# Prism.net
KiCad netlist of a schematic drawn in EAGLE
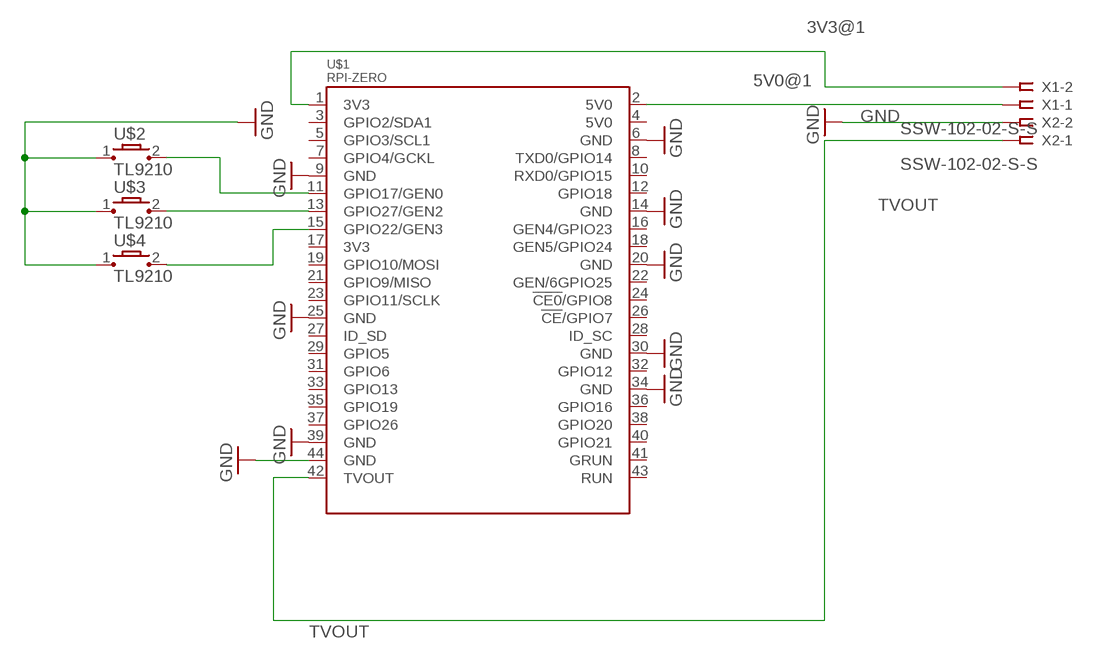
[diagram p0: schematic, sheet 1]

(export (version "E")
  (design (tool "Eeschema 10.0.6"))
  (components
    (comp (ref "U$1")
      (value "RPI-ZERO")
      (footprint "eagle-import:RASPBERRYPI_BASTELSTUBE_V13_RASPI_BOARD_B+_FULL")
      (libsource (lib "eagle-import") (part "RPI-ZERO"))
    )
    (comp (ref "U$2")
      (value "TL9210")
      (footprint "eagle-import:TL9210")
      (libsource (lib "eagle-import") (part "TL9210"))
    )
    (comp (ref "U$3")
      (value "TL9210")
      (footprint "eagle-import:TL9210")
      (libsource (lib "eagle-import") (part "TL9210"))
    )
    (comp (ref "U$4")
      (value "TL9210")
      (footprint "eagle-import:TL9210")
      (libsource (lib "eagle-import") (part "TL9210"))
    )
    (comp (ref "X1")
      (value "SSW-102-02-S-S")
      (footprint "eagle-import:SSW-102-02-S-S")
      (libsource (lib "eagle-import") (part "SSW-102-02-S-S"))
    )
    (comp (ref "X2")
      (value "SSW-102-02-S-S")
      (footprint "eagle-import:SSW-102-02-S-S")
      (libsource (lib "eagle-import") (part "SSW-102-02-S-S"))
    )
  )
  (nets
    (net (code "1") (name "/3V3") (class "Default")
      (node (ref "U$1") (pin "17") (pinfunction "3V3_17") (pintype "power_in"))
    )
    (net (code "2") (name "/3V3@1") (class "Default")
      (node (ref "U$1") (pin "1") (pinfunction "3V3_1") (pintype "power_in"))
      (node (ref "X1") (pin "2") (pinfunction "1_2") (pintype "passive"))
    )
    (net (code "3") (name "/5V0") (class "Default")
      (node (ref "U$1") (pin "4") (pinfunction "5V0_4") (pintype "power_in"))
    )
    (net (code "4") (name "/5V0@1") (class "Default")
      (node (ref "U$1") (pin "2") (pinfunction "5V0_2") (pintype "power_in"))
      (node (ref "X1") (pin "1") (pinfunction "1_1") (pintype "passive"))
    )
    (net (code "5") (name "/GRUN") (class "Default")
      (node (ref "U$1") (pin "41") (pinfunction "GRUN_41") (pintype "power_in"))
    )
    (net (code "6") (name "/TVOUT") (class "Default")
      (node (ref "U$1") (pin "42") (pinfunction "TVOUT_42") (pintype "bidirectional"))
      (node (ref "X2") (pin "1") (pinfunction "1_1") (pintype "passive"))
    )
    (net (code "7") (name "GND") (class "Default")
      (node (ref "U$1") (pin "14") (pinfunction "GND_14") (pintype "power_in"))
      (node (ref "U$1") (pin "20") (pinfunction "GND_20") (pintype "power_in"))
      (node (ref "U$1") (pin "25") (pinfunction "GND_25") (pintype "power_in"))
      (node (ref "U$1") (pin "30") (pinfunction "GND_30") (pintype "power_in"))
      (node (ref "U$1") (pin "34") (pinfunction "GND_34") (pintype "power_in"))
      (node (ref "U$1") (pin "39") (pinfunction "GND_39") (pintype "power_in"))
      (node (ref "U$1") (pin "44") (pinfunction "GND_44") (pintype "power_in"))
      (node (ref "U$1") (pin "6") (pinfunction "GND_6") (pintype "power_in"))
      (node (ref "U$1") (pin "9") (pinfunction "GND_9") (pintype "power_in"))
      (node (ref "U$2") (pin "1") (pinfunction "1_1") (pintype "passive"))
      (node (ref "U$3") (pin "1") (pinfunction "1_1") (pintype "passive"))
      (node (ref "U$4") (pin "1") (pinfunction "1_1") (pintype "passive"))
      (node (ref "X2") (pin "2") (pinfunction "1_2") (pintype "passive"))
    )
    (net (code "8") (name "Net-(U$1-GPIO17{slash}GEN0)") (class "Default")
      (node (ref "U$1") (pin "11") (pinfunction "GPIO17/GEN0_11") (pintype "bidirectional"))
      (node (ref "U$2") (pin "2") (pinfunction "2_2") (pintype "passive"))
    )
    (net (code "9") (name "Net-(U$1-GPIO22{slash}GEN3)") (class "Default")
      (node (ref "U$1") (pin "15") (pinfunction "GPIO22/GEN3_15") (pintype "bidirectional"))
      (node (ref "U$4") (pin "2") (pinfunction "2_2") (pintype "passive"))
    )
    (net (code "10") (name "Net-(U$1-GPIO27{slash}GEN2)") (class "Default")
      (node (ref "U$1") (pin "13") (pinfunction "GPIO27/GEN2_13") (pintype "bidirectional"))
      (node (ref "U$3") (pin "2") (pinfunction "2_2") (pintype "passive"))
    )
    (net (code "11") (name "unconnected-(U$1-GEN4{slash}GPIO23-Pad16)") (class "Default")
      (node (ref "U$1") (pin "16") (pinfunction "GEN4/GPIO23_16") (pintype "bidirectional"))
    )
    (net (code "12") (name "unconnected-(U$1-GEN5{slash}GPIO24-Pad18)") (class "Default")
      (node (ref "U$1") (pin "18") (pinfunction "GEN5/GPIO24_18") (pintype "bidirectional"))
    )
    (net (code "13") (name "unconnected-(U$1-GEN{slash}6GPIO25-Pad22)") (class "Default")
      (node (ref "U$1") (pin "22") (pinfunction "GEN/6GPIO25_22") (pintype "bidirectional"))
    )
    (net (code "14") (name "unconnected-(U$1-GPIO2{slash}SDA1-Pad3)") (class "Default")
      (node (ref "U$1") (pin "3") (pinfunction "GPIO2/SDA1_3") (pintype "bidirectional"))
    )
    (net (code "15") (name "unconnected-(U$1-GPIO3{slash}SCL1-Pad5)") (class "Default")
      (node (ref "U$1") (pin "5") (pinfunction "GPIO3/SCL1_5") (pintype "bidirectional"))
    )
    (net (code "16") (name "unconnected-(U$1-GPIO4{slash}GCKL-Pad7)") (class "Default")
      (node (ref "U$1") (pin "7") (pinfunction "GPIO4/GCKL_7") (pintype "bidirectional"))
    )
    (net (code "17") (name "unconnected-(U$1-GPIO5-Pad29)") (class "Default")
      (node (ref "U$1") (pin "29") (pinfunction "GPIO5_29") (pintype "bidirectional"))
    )
    (net (code "18") (name "unconnected-(U$1-GPIO6-Pad31)") (class "Default")
      (node (ref "U$1") (pin "31") (pinfunction "GPIO6_31") (pintype "bidirectional"))
    )
    (net (code "19") (name "unconnected-(U$1-GPIO9{slash}MISO-Pad21)") (class "Default")
      (node (ref "U$1") (pin "21") (pinfunction "GPIO9/MISO_21") (pintype "bidirectional"))
    )
    (net (code "20") (name "unconnected-(U$1-GPIO10{slash}MOSI-Pad19)") (class "Default")
      (node (ref "U$1") (pin "19") (pinfunction "GPIO10/MOSI_19") (pintype "bidirectional"))
    )
    (net (code "21") (name "unconnected-(U$1-GPIO11{slash}SCLK-Pad23)") (class "Default")
      (node (ref "U$1") (pin "23") (pinfunction "GPIO11/SCLK_23") (pintype "bidirectional"))
    )
    (net (code "22") (name "unconnected-(U$1-GPIO12-Pad32)") (class "Default")
      (node (ref "U$1") (pin "32") (pinfunction "GPIO12_32") (pintype "bidirectional"))
    )
    (net (code "23") (name "unconnected-(U$1-GPIO13-Pad33)") (class "Default")
      (node (ref "U$1") (pin "33") (pinfunction "GPIO13_33") (pintype "bidirectional"))
    )
    (net (code "24") (name "unconnected-(U$1-GPIO16-Pad36)") (class "Default")
      (node (ref "U$1") (pin "36") (pinfunction "GPIO16_36") (pintype "bidirectional"))
    )
    (net (code "25") (name "unconnected-(U$1-GPIO18-Pad12)") (class "Default")
      (node (ref "U$1") (pin "12") (pinfunction "GPIO18_12") (pintype "bidirectional"))
    )
    (net (code "26") (name "unconnected-(U$1-GPIO19-Pad35)") (class "Default")
      (node (ref "U$1") (pin "35") (pinfunction "GPIO19_35") (pintype "bidirectional"))
    )
    (net (code "27") (name "unconnected-(U$1-GPIO20-Pad38)") (class "Default")
      (node (ref "U$1") (pin "38") (pinfunction "GPIO20_38") (pintype "bidirectional"))
    )
    (net (code "28") (name "unconnected-(U$1-GPIO21-Pad40)") (class "Default")
      (node (ref "U$1") (pin "40") (pinfunction "GPIO21_40") (pintype "bidirectional"))
    )
    (net (code "29") (name "unconnected-(U$1-GPIO26-Pad37)") (class "Default")
      (node (ref "U$1") (pin "37") (pinfunction "GPIO26_37") (pintype "bidirectional"))
    )
    (net (code "30") (name "unconnected-(U$1-ID_SC-Pad28)") (class "Default")
      (node (ref "U$1") (pin "28") (pinfunction "ID_SC_28") (pintype "bidirectional"))
    )
    (net (code "31") (name "unconnected-(U$1-ID_SD-Pad27)") (class "Default")
      (node (ref "U$1") (pin "27") (pinfunction "ID_SD_27") (pintype "bidirectional"))
    )
    (net (code "32") (name "unconnected-(U$1-RUN-Pad43)") (class "Default")
      (node (ref "U$1") (pin "43") (pinfunction "RUN_43") (pintype "bidirectional"))
    )
    (net (code "33") (name "unconnected-(U$1-RXD0{slash}GPIO15-Pad10)") (class "Default")
      (node (ref "U$1") (pin "10") (pinfunction "RXD0/GPIO15_10") (pintype "bidirectional"))
    )
    (net (code "34") (name "unconnected-(U$1-TXD0{slash}GPIO14-Pad8)") (class "Default")
      (node (ref "U$1") (pin "8") (pinfunction "TXD0/GPIO14_8") (pintype "bidirectional"))
    )
    (net (code "35") (name "unconnected-(U$1-~{CE0}{slash}GPIO8-Pad24)") (class "Default")
      (node (ref "U$1") (pin "24") (pinfunction "~{CE0}/GPIO8_24") (pintype "bidirectional"))
    )
    (net (code "36") (name "unconnected-(U$1-~{CE}{slash}GPIO7-Pad26)") (class "Default")
      (node (ref "U$1") (pin "26") (pinfunction "~{CE}/GPIO7_26") (pintype "bidirectional"))
    )
  )
)
